# NFC.net
KiCad netlist of a schematic drawn in Altium Designer
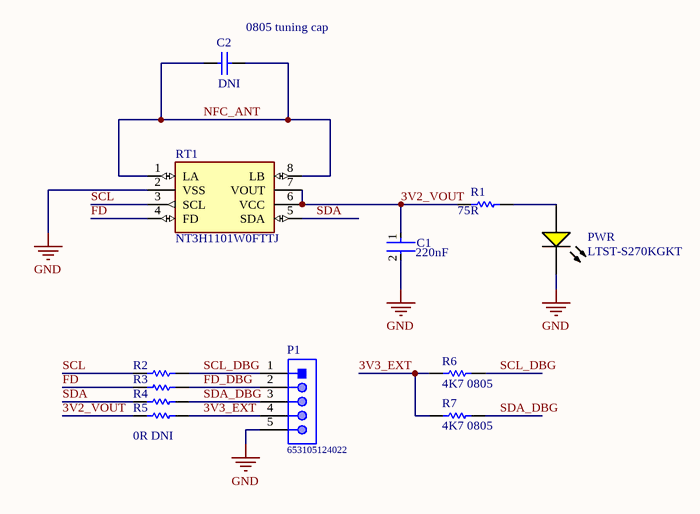
[diagram p0: NFC.SchDoc]

(export (version "E")
  (design (tool "Eeschema 10.0.6"))
  (components
    (comp (ref "C1")
      (value "220nF")
      (footprint "FP-CC0805-0_85-MFG")
      (description "CAP CER 0.22UF 16V X7R 0805")
      (fields (field (name "TOLERANCE") "0.1") (field (name "MANUFACTURER") "Yageo"))
      (libsource (lib "Altium Content Vault") (part "11868f565c42a9108669ba33697ecf6"))
    )
    (comp (ref "C2")
      (value "DNI")
      (footprint "CAPC2013X140X50ML20T25")
      (fields
        (field (name "MANUFACTURER") "AVX Interconnect / Elco")
        (field (name "PART NUMBER") "08051A1R0CAT2A")
      )
      (libsource (lib "Altium Content Vault") (part "CAP"))
    )
    (comp (ref "P1")
      (value "653105124022")
      (footprint "653105124022")
      (description "Male Shrouded Header WR-WTB, SMT, Vertical, pitch 1.25 mm, 1 x 5 position")
      (fields (field (name "MANUFACTURER") "Wurth Elektronik") (field (name "PUBLISHER") "WurthElektronik"))
      (libsource (lib "Altium Content Vault") (part "WE-CN-1P-M-R5"))
    )
    (comp (ref "PWR")
      (value "LTST-S270KGKT")
      (footprint "AVAG-HSMX-C190_V")
      (description "LED Uni-Color Yellow, 65 mW, 20 mA, -40 to 85 degC, 2-Pin SMD, RoHS, Tape and Reel")
      (fields (field (name "TOLERANCE") "1%"))
      (libsource (lib "Altium Content Vault") (part "LED-YELLOW-AK-2"))
    )
    (comp (ref "R1")
      (value "75R")
      (footprint "RESC2013X50X30LL20T20")
      (fields (field (name "MANUFACTURER") "Vishay Dale") (field (name "PART NUMBER") "CRCW08050000Z0EA"))
      (libsource (lib "Altium Content Vault") (part "RES"))
    )
    (comp (ref "R2")
      (value "0R DNI")
      (footprint "RESC2013X60X35ML10T20")
      (fields (field (name "TOLERANCE") "5%") (field (name "MANUFACTURER") "Yageo"))
      (libsource (lib "Altium Content Vault") (part "RES-2"))
    )
    (comp (ref "R3")
      (value "RC0805JR-070RL")
      (footprint "RESC2013X60X35ML10T20")
      (fields (field (name "TOLERANCE") "5%") (field (name "MANUFACTURER") "Yageo"))
      (libsource (lib "Altium Content Vault") (part "RES-2"))
    )
    (comp (ref "R4")
      (value "RC0805JR-070RL")
      (footprint "RESC2013X60X35ML10T20")
      (fields (field (name "TOLERANCE") "5%") (field (name "MANUFACTURER") "Yageo"))
      (libsource (lib "Altium Content Vault") (part "RES-2"))
    )
    (comp (ref "R5")
      (value "RC0805JR-070RL")
      (footprint "RESC2013X60X35ML10T20")
      (fields (field (name "TOLERANCE") "5%") (field (name "MANUFACTURER") "Yageo"))
      (libsource (lib "Altium Content Vault") (part "RES-2"))
    )
    (comp (ref "R6")
      (value "4K7 0805")
      (footprint "YAGO-RC0805_M")
      (fields
        (field (name "TOLERANCE") "+/- 1%")
        (field (name "PARTNUMBER") "RC0805FR-074K7L")
        (field (name "POWER") "0.125 W")
      )
      (libsource (lib "Altium Content Vault") (part "YAGO-RES-2"))
    )
    (comp (ref "R7")
      (value "4K7 0805")
      (footprint "YAGO-RC0805_M")
      (fields
        (field (name "TOLERANCE") "+/- 1%")
        (field (name "PARTNUMBER") "RC0805FR-074K7L")
        (field (name "POWER") "0.125 W")
      )
      (libsource (lib "Altium Content Vault") (part "YAGO-RES-2"))
    )
    (comp (ref "RT1")
      (value "NT3H1101W0FTTJ")
      (footprint "SamacSys:SOP65P490X110-8N")
      (description "Thermistor")
      (fields (field (name "MOUSER PART NUMBER") "771-NT3H1101W0FTTJ"))
      (libsource (lib "*") (part "NT3H1101W0FTTJ"))
    )
  )
  (nets
    (net (code "1") (name "/3V2_VOUT") (class "Default")
      (node (ref "C1") (pin "1") (pinfunction "1_1") (pintype "passive"))
      (node (ref "R1") (pin "1") (pinfunction "1_1") (pintype "passive"))
      (node (ref "R5") (pin "1") (pinfunction "1_1") (pintype "passive"))
      (node (ref "RT1") (pin "6") (pinfunction "VCC_6") (pintype "power_in"))
      (node (ref "RT1") (pin "7") (pinfunction "VOUT_7") (pintype "power_in"))
    )
    (net (code "2") (name "/3V3_EXT") (class "Default")
      (node (ref "P1") (pin "4") (pinfunction "4_4") (pintype "passive"))
      (node (ref "R5") (pin "2") (pinfunction "2_2") (pintype "passive"))
      (node (ref "R6") (pin "1") (pinfunction "1_1") (pintype "passive"))
      (node (ref "R7") (pin "1") (pinfunction "1_1") (pintype "passive"))
    )
    (net (code "3") (name "/FD") (class "Default")
      (node (ref "R3") (pin "1") (pinfunction "1_1") (pintype "passive"))
      (node (ref "RT1") (pin "4") (pinfunction "FD_4") (pintype "bidirectional"))
    )
    (net (code "4") (name "/FD_DBG") (class "Default")
      (node (ref "P1") (pin "2") (pinfunction "2_2") (pintype "passive"))
      (node (ref "R3") (pin "2") (pinfunction "2_2") (pintype "passive"))
    )
    (net (code "5") (name "/NFC_ANT") (class "Default")
      (node (ref "C2") (pin "1") (pinfunction "1_1") (pintype "passive"))
      (node (ref "C2") (pin "2") (pinfunction "2_2") (pintype "passive"))
      (node (ref "RT1") (pin "1") (pinfunction "LA_1") (pintype "bidirectional"))
      (node (ref "RT1") (pin "8") (pinfunction "LB_8") (pintype "bidirectional"))
    )
    (net (code "6") (name "/SCL") (class "Default")
      (node (ref "R2") (pin "1") (pinfunction "1_1") (pintype "passive"))
      (node (ref "RT1") (pin "3") (pinfunction "SCL_3") (pintype "output"))
    )
    (net (code "7") (name "/SCL_DBG") (class "Default")
      (node (ref "P1") (pin "1") (pinfunction "1_1") (pintype "passive"))
      (node (ref "R2") (pin "2") (pinfunction "2_2") (pintype "passive"))
      (node (ref "R6") (pin "2") (pinfunction "2_2") (pintype "passive"))
    )
    (net (code "8") (name "/SDA") (class "Default")
      (node (ref "R4") (pin "1") (pinfunction "1_1") (pintype "passive"))
      (node (ref "RT1") (pin "5") (pinfunction "SDA_5") (pintype "bidirectional"))
    )
    (net (code "9") (name "/SDA_DBG") (class "Default")
      (node (ref "P1") (pin "3") (pinfunction "3_3") (pintype "passive"))
      (node (ref "R4") (pin "2") (pinfunction "2_2") (pintype "passive"))
      (node (ref "R7") (pin "2") (pinfunction "2_2") (pintype "passive"))
    )
    (net (code "10") (name "GND") (class "Default")
      (node (ref "C1") (pin "2") (pinfunction "2_2") (pintype "passive"))
      (node (ref "P1") (pin "5") (pinfunction "5_5") (pintype "passive"))
      (node (ref "PWR") (pin "2") (pinfunction "K_2") (pintype "passive"))
      (node (ref "RT1") (pin "2") (pinfunction "VSS_2") (pintype "power_in"))
    )
    (net (code "11") (name "Net-(PWR-A)") (class "Default")
      (node (ref "PWR") (pin "1") (pinfunction "A_1") (pintype "passive"))
      (node (ref "R1") (pin "2") (pinfunction "2_2") (pintype "passive"))
    )
  )
)
